# power.net
KiCad netlist of a schematic drawn in Altium Designer
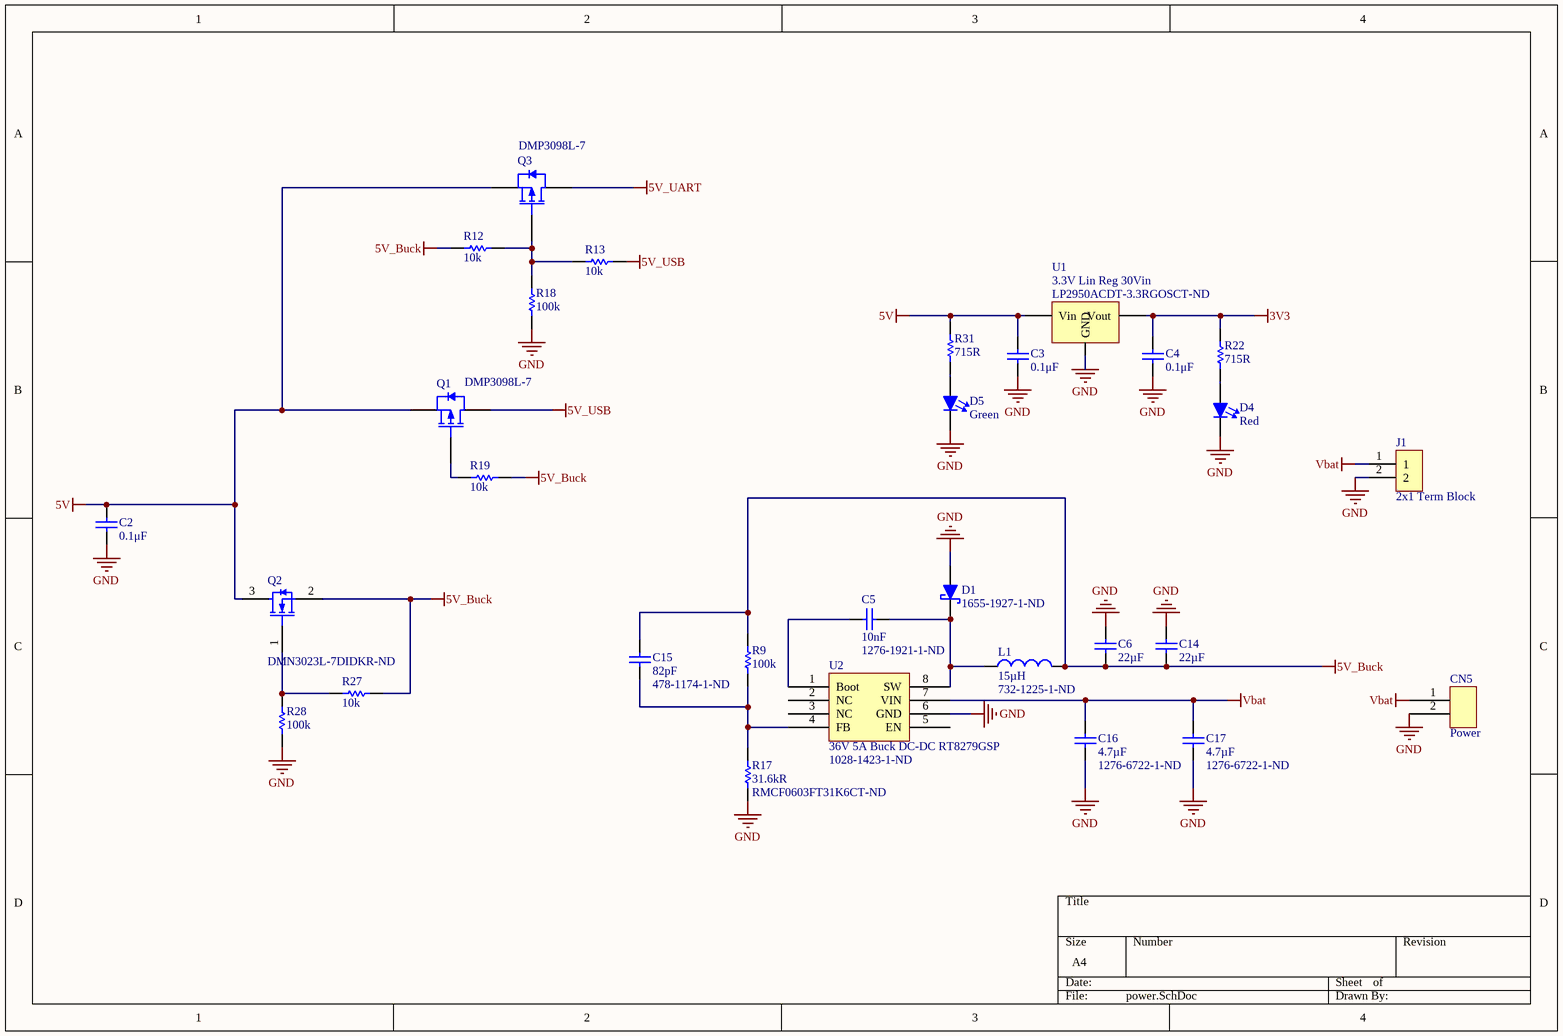
[diagram p0: power.SchDoc]

(export (version "E")
  (design (tool "Eeschema 10.0.6"))
  (components
    (comp (ref "C2")
      (value "0.1μF")
      (footprint "CAPC1608N(0603\")")
      (description "Capacitor, Ceramic, 100V, +/- 10%, 0603 SMD, X7R")
      (fields
        (field (name "MFG") "TDK")
        (field (name "PUBLISHER") "AUVic")
        (field (name "CREATED BY") "Ashwin Sira")
      )
      (libsource (lib "AUVic_Integrated_Library_Capacitors") (part "0.1uF 100V 0603 SMD, Ceramic"))
    )
    (comp (ref "C3")
      (value "0.1μF")
      (footprint "CAPC1608N(0603\")")
      (description "Capacitor, Ceramic, 100V, +/- 10%, 0603 SMD, X7R")
      (fields
        (field (name "MFG") "TDK")
        (field (name "PUBLISHER") "AUVic")
        (field (name "CREATED BY") "Ashwin Sira")
      )
      (libsource (lib "AUVic_Integrated_Library_Capacitors") (part "0.1uF 100V 0603 SMD, Ceramic"))
    )
    (comp (ref "C4")
      (value "0.1μF")
      (footprint "CAPC1608N(0603\")")
      (description "Capacitor, Ceramic, 100V, +/- 10%, 0603 SMD, X7R")
      (fields
        (field (name "MFG") "TDK")
        (field (name "PUBLISHER") "AUVic")
        (field (name "CREATED BY") "Ashwin Sira")
      )
      (libsource (lib "AUVic_Integrated_Library_Capacitors") (part "0.1uF 100V 0603 SMD, Ceramic"))
    )
    (comp (ref "C5")
      (value "10nF")
      (footprint "CAPC1608N(0603\")")
      (description "Capacitor, Ceramic, 50V, +/- 10%, 0603 SMD")
      (fields
        (field (name "MFG") "Samsung")
        (field (name "SUPPLIER PART NUMBER 1") "1276-1921-1-ND")
        (field (name "PUBLISHER") "AUVic")
        (field (name "CREATED BY") "Gabriel")
      )
      (libsource (lib "AUVic_Integrated_Library_Capacitors") (part "10 nF, 50V 0603 SMD, Ceramic"))
    )
    (comp (ref "C6")
      (value "22µF")
      (footprint "CAPC2012N(0805\")")
      (description "Capacitor, Ceramic, 35V, +/- 20%, 0805 SMD, X5R")
      (fields (field (name "PUBLISHER") "AUVic"))
      (libsource (lib "AUVic_Integrated_Library_Capacitors") (part "22uF 35V 0805 SMD, Ceramic"))
    )
    (comp (ref "C14")
      (value "22µF")
      (footprint "CAPC2012N(0805\")")
      (description "Capacitor, Ceramic, 35V, +/- 20%, 0805 SMD, X5R")
      (fields (field (name "PUBLISHER") "AUVic"))
      (libsource (lib "AUVic_Integrated_Library_Capacitors") (part "22uF 35V 0805 SMD, Ceramic"))
    )
    (comp (ref "C15")
      (value "82pF")
      (footprint "CAPC1608N(0603\")")
      (description "82pF 50V Ceramic Capacitor C0G, NP0 0603")
      (fields
        (field (name "SUPPLIER PART NUMBER 1") "478-1174-1-ND")
        (field (name "CREATED BY") "Robert Keen")
      )
      (libsource (lib "AUVic_Integrated_Library_Capacitors") (part "82pF 50V 0603 SMD, Ceramic"))
    )
    (comp (ref "C16")
      (value "4.7µF")
      (footprint "CAPC2012N(0805\")")
      (description "Capacitor, Ceramic, 35V, +/- 10%, 0805 SMD, X5R")
      (fields
        (field (name "SUPPLIER PART NUMBER 1") "1276-6722-1-ND")
        (field (name "PUBLISHER") "AUVic")
        (field (name "MADE BY") "Andy Bates")
      )
      (libsource (lib "AUVic_Integrated_Library_Capacitors") (part "4.7uF 35V 0805 SMD, Ceramic"))
    )
    (comp (ref "C17")
      (value "4.7µF")
      (footprint "CAPC2012N(0805\")")
      (description "Capacitor, Ceramic, 35V, +/- 10%, 0805 SMD, X5R")
      (fields
        (field (name "SUPPLIER PART NUMBER 1") "1276-6722-1-ND")
        (field (name "PUBLISHER") "AUVic")
        (field (name "MADE BY") "Andy Bates")
      )
      (libsource (lib "AUVic_Integrated_Library_Capacitors") (part "4.7uF 35V 0805 SMD, Ceramic"))
    )
    (comp (ref "CN5")
      (value "Power")
      (footprint "2X1 Power Connector 90 degrees")
      (description "Connector Header Through Hole, Right Angle 2 position 0.312\" (7.92mm)")
      (fields (field (name "MADE BY") "Robert Keen"))
      (libsource (lib "AUVic_Integrated_Library_Connectors") (part "2x1, Male header, Right Angle, Latch holder"))
    )
    (comp (ref "D1")
      (value "DSS14UTR")
      (footprint "SOD-123F")
      (description "Diode, Schottky, 40V, 1A")
      (fields
        (field (name "SUPPLIER PART NUMBER 1") "1655-1927-1-ND")
        (field (name "CREATED BY") "Robert Keen")
        (field (name "PUBLISHER") "AUVic")
      )
      (libsource (lib "AUVic_Integrated_Library_Diodes") (part "DSS14UTR"))
    )
    (comp (ref "D4")
      (value "Red")
      (footprint "LED0805")
      (description "LED, 0805 (2012), Red, Clear")
      (fields (field (name "CREATED BY") "Ashwin Sira"))
      (libsource (lib "AUVic_Integrated_Library_Diodes") (part "LED, 0805 (2012), Red, Clear"))
    )
    (comp (ref "D5")
      (value "Green")
      (footprint "LED0805")
      (description "LED, 0805 (2012), Green, Clear")
      (fields (field (name "CREATED BY") "Andy Bates"))
      (libsource (lib "AUVic_Integrated_Library_Diodes") (part "LED, 0805 (2012), Green, Clear"))
    )
    (comp (ref "J1")
      (value "2x1 Term Block")
      (footprint "2X1 Terminal Blocks")
      (fields (field (name "MADE BY") "Andy Bates"))
      (libsource (lib "AUVic_Integrated_Library_Connectors") (part "2x1 Terminal Block"))
    )
    (comp (ref "L1")
      (value "15µH")
      (footprint "WE-PD-XL")
      (description "15µH Shielded Wirewound Inductor 5A 27 mOhm Max Nonstandard")
      (fields
        (field (name "SUPPLIER PART NUMBER 1") "732-1225-1-ND")
        (field (name "CREATED BY") "Robert Keen")
      )
      (libsource (lib "AUVic_Integrated_Library_Inductors") (part "15µH 5A Inductor"))
    )
    (comp (ref "Q1")
      (value "DMP3098L-7")
      (footprint "DIOD-SOT23-3_V")
      (description "P-Channel Enhancement Mode MOSFET, -30 V VDS, -55 to 155 degC, 3-Pin SOT23, RoHS, Tape and Reel")
      (fields (field (name "MANUFACTURER") "Diodes Inc"))
      (libsource (lib "Altium Content Vault") (part "DIOD-PEMOS-G1S2D3-3"))
    )
    (comp (ref "Q2")
      (value "MOSFET N-Channel, 30V, 6.2A,")
      (footprint "SOT-23")
      (description "N-Channel 30V 6.2A (Ta) 900mW (Ta) Surface Mount SOT-23")
      (fields
        (field (name "SUPPLIER PART NUMBER 1") "DMN3023L-7DIDKR-ND")
        (field (name "CREATED BY") "Poorna Chander Kalidas")
      )
      (libsource (lib "AUVic_Integrated_Library_Transistors") (part "MOSFET N-Channel, 30V, 6.2A,"))
    )
    (comp (ref "Q3")
      (value "DMP3098L-7")
      (footprint "DIOD-SOT23-3_V")
      (description "P-Channel Enhancement Mode MOSFET, -30 V VDS, -55 to 155 degC, 3-Pin SOT23, RoHS, Tape and Reel")
      (fields (field (name "MANUFACTURER") "Diodes Inc"))
      (libsource (lib "Altium Content Vault") (part "DIOD-PEMOS-G1S2D3-3"))
    )
    (comp (ref "R9")
      (value "100k")
      (footprint "RESC1608N(0603\")")
      (description "100kR, 1%, 1/10W, 0603 SMD")
      (fields (field (name "MADE BY") "Andy Bates"))
      (libsource (lib "AUVic_Integrated_Library_Resistors") (part "100kR, 1%, 1/10W, 0603 SMD"))
    )
    (comp (ref "R12")
      (value "10k")
      (footprint "RESC1608N(0603\")")
      (description "10kR, 1%, 1/10W, 0603 SMD")
      (fields (field (name "MADE BY") "Ashwin Sira"))
      (libsource (lib "AUVic_Integrated_Library_Resistors") (part "10kR, 1%, 1/10W, 0603 SMD"))
    )
    (comp (ref "R13")
      (value "10k")
      (footprint "RESC1608N(0603\")")
      (description "10kR, 1%, 1/10W, 0603 SMD")
      (fields (field (name "MADE BY") "Ashwin Sira"))
      (libsource (lib "AUVic_Integrated_Library_Resistors") (part "10kR, 1%, 1/10W, 0603 SMD"))
    )
    (comp (ref "R17")
      (value "31.6kR")
      (footprint "RESC1608N(0603\")")
      (description "31.6kR, 1%, 1/10W, 0603, SMD")
      (fields
        (field (name "SUPPLIER PART NUMBER 1") "RMCF0603FT31K6CT-ND")
        (field (name "CREATED BY") "Robert Keen")
      )
      (libsource (lib "AUVic_Integrated_Library_Resistors") (part "31.6kR, 1%, 1/10W, 0603, SMD"))
    )
    (comp (ref "R18")
      (value "100k")
      (footprint "RESC1608N(0603\")")
      (description "100kR, 1%, 1/10W, 0603 SMD")
      (fields (field (name "MADE BY") "Andy Bates"))
      (libsource (lib "AUVic_Integrated_Library_Resistors") (part "100kR, 1%, 1/10W, 0603 SMD"))
    )
    (comp (ref "R19")
      (value "10k")
      (footprint "RESC1608N(0603\")")
      (description "10kR, 1%, 1/10W, 0603 SMD")
      (fields (field (name "MADE BY") "Ashwin Sira"))
      (libsource (lib "AUVic_Integrated_Library_Resistors") (part "10kR, 1%, 1/10W, 0603 SMD"))
    )
    (comp (ref "R22")
      (value "715R")
      (footprint "RESC1608N(0603\")")
      (description "715R, 1%, 1/10W, 0603, SMD")
      (fields (field (name "CREATED BY") "Ashwin Sira") (field (name "PUBLISHER") "AUVic"))
      (libsource (lib "AUVic_Integrated_Library_Resistors") (part "715R, 1%, 1/10W, 0603, SMD"))
    )
    (comp (ref "R27")
      (value "10k")
      (footprint "RESC1608N(0603\")")
      (description "10kR, 1%, 1/10W, 0603 SMD")
      (fields (field (name "MADE BY") "Ashwin Sira"))
      (libsource (lib "AUVic_Integrated_Library_Resistors") (part "10kR, 1%, 1/10W, 0603 SMD"))
    )
    (comp (ref "R28")
      (value "100k")
      (footprint "RESC1608N(0603\")")
      (description "100kR, 1%, 1/10W, 0603 SMD")
      (fields (field (name "MADE BY") "Andy Bates"))
      (libsource (lib "AUVic_Integrated_Library_Resistors") (part "100kR, 1%, 1/10W, 0603 SMD"))
    )
    (comp (ref "R31")
      (value "715R")
      (footprint "RESC1608N(0603\")")
      (description "715R, 1%, 1/10W, 0603, SMD")
      (fields (field (name "CREATED BY") "Ashwin Sira") (field (name "PUBLISHER") "AUVic"))
      (libsource (lib "AUVic_Integrated_Library_Resistors") (part "715R, 1%, 1/10W, 0603, SMD"))
    )
    (comp (ref "U1")
      (value "3.3V Lin Reg 30Vin")
      (footprint "T0-252")
      (fields (field (name "SUPPLIER PART NUMBER 1") "LP2950ACDT-3.3RGOSCT-ND"))
      (libsource (lib "AUVic_Integrated_Library_Regulators") (part "3.3V TO-252 Linear Regulator"))
    )
    (comp (ref "U2")
      (value "36V 5A Buck DC-DC RT8279GSP")
      (footprint "8-SOP-EP")
      (fields (field (name "SUPPLIER PART NUMBER 3") "1028-1423-1-ND") (field (name "MADE BY") "Robert Keen"))
      (libsource (lib "AUVic_Integrated_Library_Regulators") (part "36V 5A Buck DC-DC RT8279GSP"))
    )
  )
  (nets
    (net (code "1") (name "3V3") (class "Default")
      (node (ref "C4") (pin "2") (pinfunction "Cathode_2") (pintype "passive"))
      (node (ref "R22") (pin "2") (pinfunction "2_2") (pintype "passive"))
      (node (ref "U1") (pin "3") (pinfunction "Vout_3") (pintype "passive"))
    )
    (net (code "2") (name "5V") (class "Default")
      (node (ref "C2") (pin "2") (pinfunction "Cathode_2") (pintype "passive"))
      (node (ref "C3") (pin "2") (pinfunction "Cathode_2") (pintype "passive"))
      (node (ref "Q1") (pin "2") (pinfunction "S_2") (pintype "passive"))
      (node (ref "Q2") (pin "3") (pinfunction "Drain_3") (pintype "passive"))
      (node (ref "Q3") (pin "2") (pinfunction "S_2") (pintype "passive"))
      (node (ref "R31") (pin "2") (pinfunction "2_2") (pintype "passive"))
      (node (ref "U1") (pin "2") (pinfunction "Vin_2") (pintype "passive"))
    )
    (net (code "3") (name "5V_Buck") (class "Default")
      (node (ref "C14") (pin "1") (pinfunction "Anode_1") (pintype "passive"))
      (node (ref "C15") (pin "2") (pinfunction "2_2") (pintype "passive"))
      (node (ref "C6") (pin "1") (pinfunction "Anode_1") (pintype "passive"))
      (node (ref "L1") (pin "2") (pinfunction "2_2") (pintype "passive"))
      (node (ref "Q2") (pin "2") (pinfunction "Source_2") (pintype "passive"))
      (node (ref "R12") (pin "1") (pinfunction "1_1") (pintype "passive"))
      (node (ref "R19") (pin "2") (pinfunction "2_2") (pintype "passive"))
      (node (ref "R27") (pin "2") (pinfunction "2_2") (pintype "passive"))
      (node (ref "R9") (pin "2") (pinfunction "2_2") (pintype "passive"))
    )
    (net (code "4") (name "5V_UART") (class "Default")
      (node (ref "Q3") (pin "3") (pinfunction "D_3") (pintype "passive"))
    )
    (net (code "5") (name "5V_USB") (class "Default")
      (node (ref "Q1") (pin "3") (pinfunction "D_3") (pintype "passive"))
      (node (ref "R13") (pin "2") (pinfunction "2_2") (pintype "passive"))
    )
    (net (code "6") (name "GND") (class "Default")
      (node (ref "C14") (pin "2") (pinfunction "Cathode_2") (pintype "passive"))
      (node (ref "C16") (pin "2") (pinfunction "Cathode_2") (pintype "passive"))
      (node (ref "C17") (pin "2") (pinfunction "Cathode_2") (pintype "passive"))
      (node (ref "C2") (pin "1") (pinfunction "Anode_1") (pintype "passive"))
      (node (ref "C3") (pin "1") (pinfunction "Anode_1") (pintype "passive"))
      (node (ref "C4") (pin "1") (pinfunction "Anode_1") (pintype "passive"))
      (node (ref "C6") (pin "2") (pinfunction "Cathode_2") (pintype "passive"))
      (node (ref "CN5") (pin "2") (pintype "passive"))
      (node (ref "D1") (pin "A") (pinfunction "Anode_A") (pintype "passive"))
      (node (ref "D4") (pin "1") (pinfunction "Cathode_1") (pintype "passive"))
      (node (ref "D5") (pin "1") (pinfunction "Cathode_1") (pintype "passive"))
      (node (ref "J1") (pin "2") (pinfunction "2_2") (pintype "passive"))
      (node (ref "R17") (pin "1") (pinfunction "1_1") (pintype "passive"))
      (node (ref "R18") (pin "1") (pinfunction "1_1") (pintype "passive"))
      (node (ref "R28") (pin "1") (pinfunction "1_1") (pintype "passive"))
      (node (ref "U1") (pin "1") (pinfunction "GND_1") (pintype "passive"))
      (node (ref "U2") (pin "6") (pinfunction "GND_6") (pintype "passive"))
    )
    (net (code "7") (name "Net-(C5-Anode)") (class "Default")
      (node (ref "C5") (pin "1") (pinfunction "Anode_1") (pintype "passive"))
      (node (ref "D1") (pin "K") (pinfunction "Cathode_K") (pintype "passive"))
      (node (ref "L1") (pin "1") (pinfunction "1_1") (pintype "passive"))
      (node (ref "U2") (pin "8") (pinfunction "SW_8") (pintype "passive"))
    )
    (net (code "8") (name "Net-(C5-Cathode)") (class "Default")
      (node (ref "C5") (pin "2") (pinfunction "Cathode_2") (pintype "passive"))
      (node (ref "U2") (pin "1") (pinfunction "Boot_1") (pintype "passive"))
    )
    (net (code "9") (name "Net-(D4-Anode)") (class "Default")
      (node (ref "D4") (pin "2") (pinfunction "Anode_2") (pintype "passive"))
      (node (ref "R22") (pin "1") (pinfunction "1_1") (pintype "passive"))
    )
    (net (code "10") (name "Net-(D5-Anode)") (class "Default")
      (node (ref "D5") (pin "2") (pinfunction "Anode_2") (pintype "passive"))
      (node (ref "R31") (pin "1") (pinfunction "1_1") (pintype "passive"))
    )
    (net (code "11") (name "Net-(Q1-G)") (class "Default")
      (node (ref "Q1") (pin "1") (pinfunction "G_1") (pintype "passive"))
      (node (ref "R19") (pin "1") (pinfunction "1_1") (pintype "passive"))
    )
    (net (code "12") (name "Net-(Q2-Gate)") (class "Default")
      (node (ref "Q2") (pin "1") (pinfunction "Gate_1") (pintype "passive"))
      (node (ref "R27") (pin "1") (pinfunction "1_1") (pintype "passive"))
      (node (ref "R28") (pin "2") (pinfunction "2_2") (pintype "passive"))
    )
    (net (code "13") (name "Net-(Q3-G)") (class "Default")
      (node (ref "Q3") (pin "1") (pinfunction "G_1") (pintype "passive"))
      (node (ref "R12") (pin "2") (pinfunction "2_2") (pintype "passive"))
      (node (ref "R13") (pin "1") (pinfunction "1_1") (pintype "passive"))
      (node (ref "R18") (pin "2") (pinfunction "2_2") (pintype "passive"))
    )
    (net (code "14") (name "Net-(U2-FB)") (class "Default")
      (node (ref "C15") (pin "1") (pinfunction "1_1") (pintype "passive"))
      (node (ref "R17") (pin "2") (pinfunction "2_2") (pintype "passive"))
      (node (ref "R9") (pin "1") (pinfunction "1_1") (pintype "passive"))
      (node (ref "U2") (pin "4") (pinfunction "FB_4") (pintype "passive"))
    )
    (net (code "15") (name "Vbat") (class "Default")
      (node (ref "C16") (pin "1") (pinfunction "Anode_1") (pintype "passive"))
      (node (ref "C17") (pin "1") (pinfunction "Anode_1") (pintype "passive"))
      (node (ref "CN5") (pin "1") (pintype "passive"))
      (node (ref "J1") (pin "1") (pinfunction "1_1") (pintype "passive"))
      (node (ref "U2") (pin "7") (pinfunction "VIN_7") (pintype "passive"))
    )
    (net (code "16") (name "unconnected-(U2-EN-Pad5)") (class "Default")
      (node (ref "U2") (pin "5") (pinfunction "EN_5") (pintype "passive"))
    )
    (net (code "17") (name "unconnected-(U2-NC-Pad2)") (class "Default")
      (node (ref "U2") (pin "2") (pinfunction "NC_2") (pintype "passive"))
    )
    (net (code "18") (name "unconnected-(U2-NC-Pad3)") (class "Default")
      (node (ref "U2") (pin "3") (pinfunction "NC_3") (pintype "passive"))
    )
  )
)
